# Simple_-V10.net
KiCad netlist of a schematic drawn in EasyEDA Pro
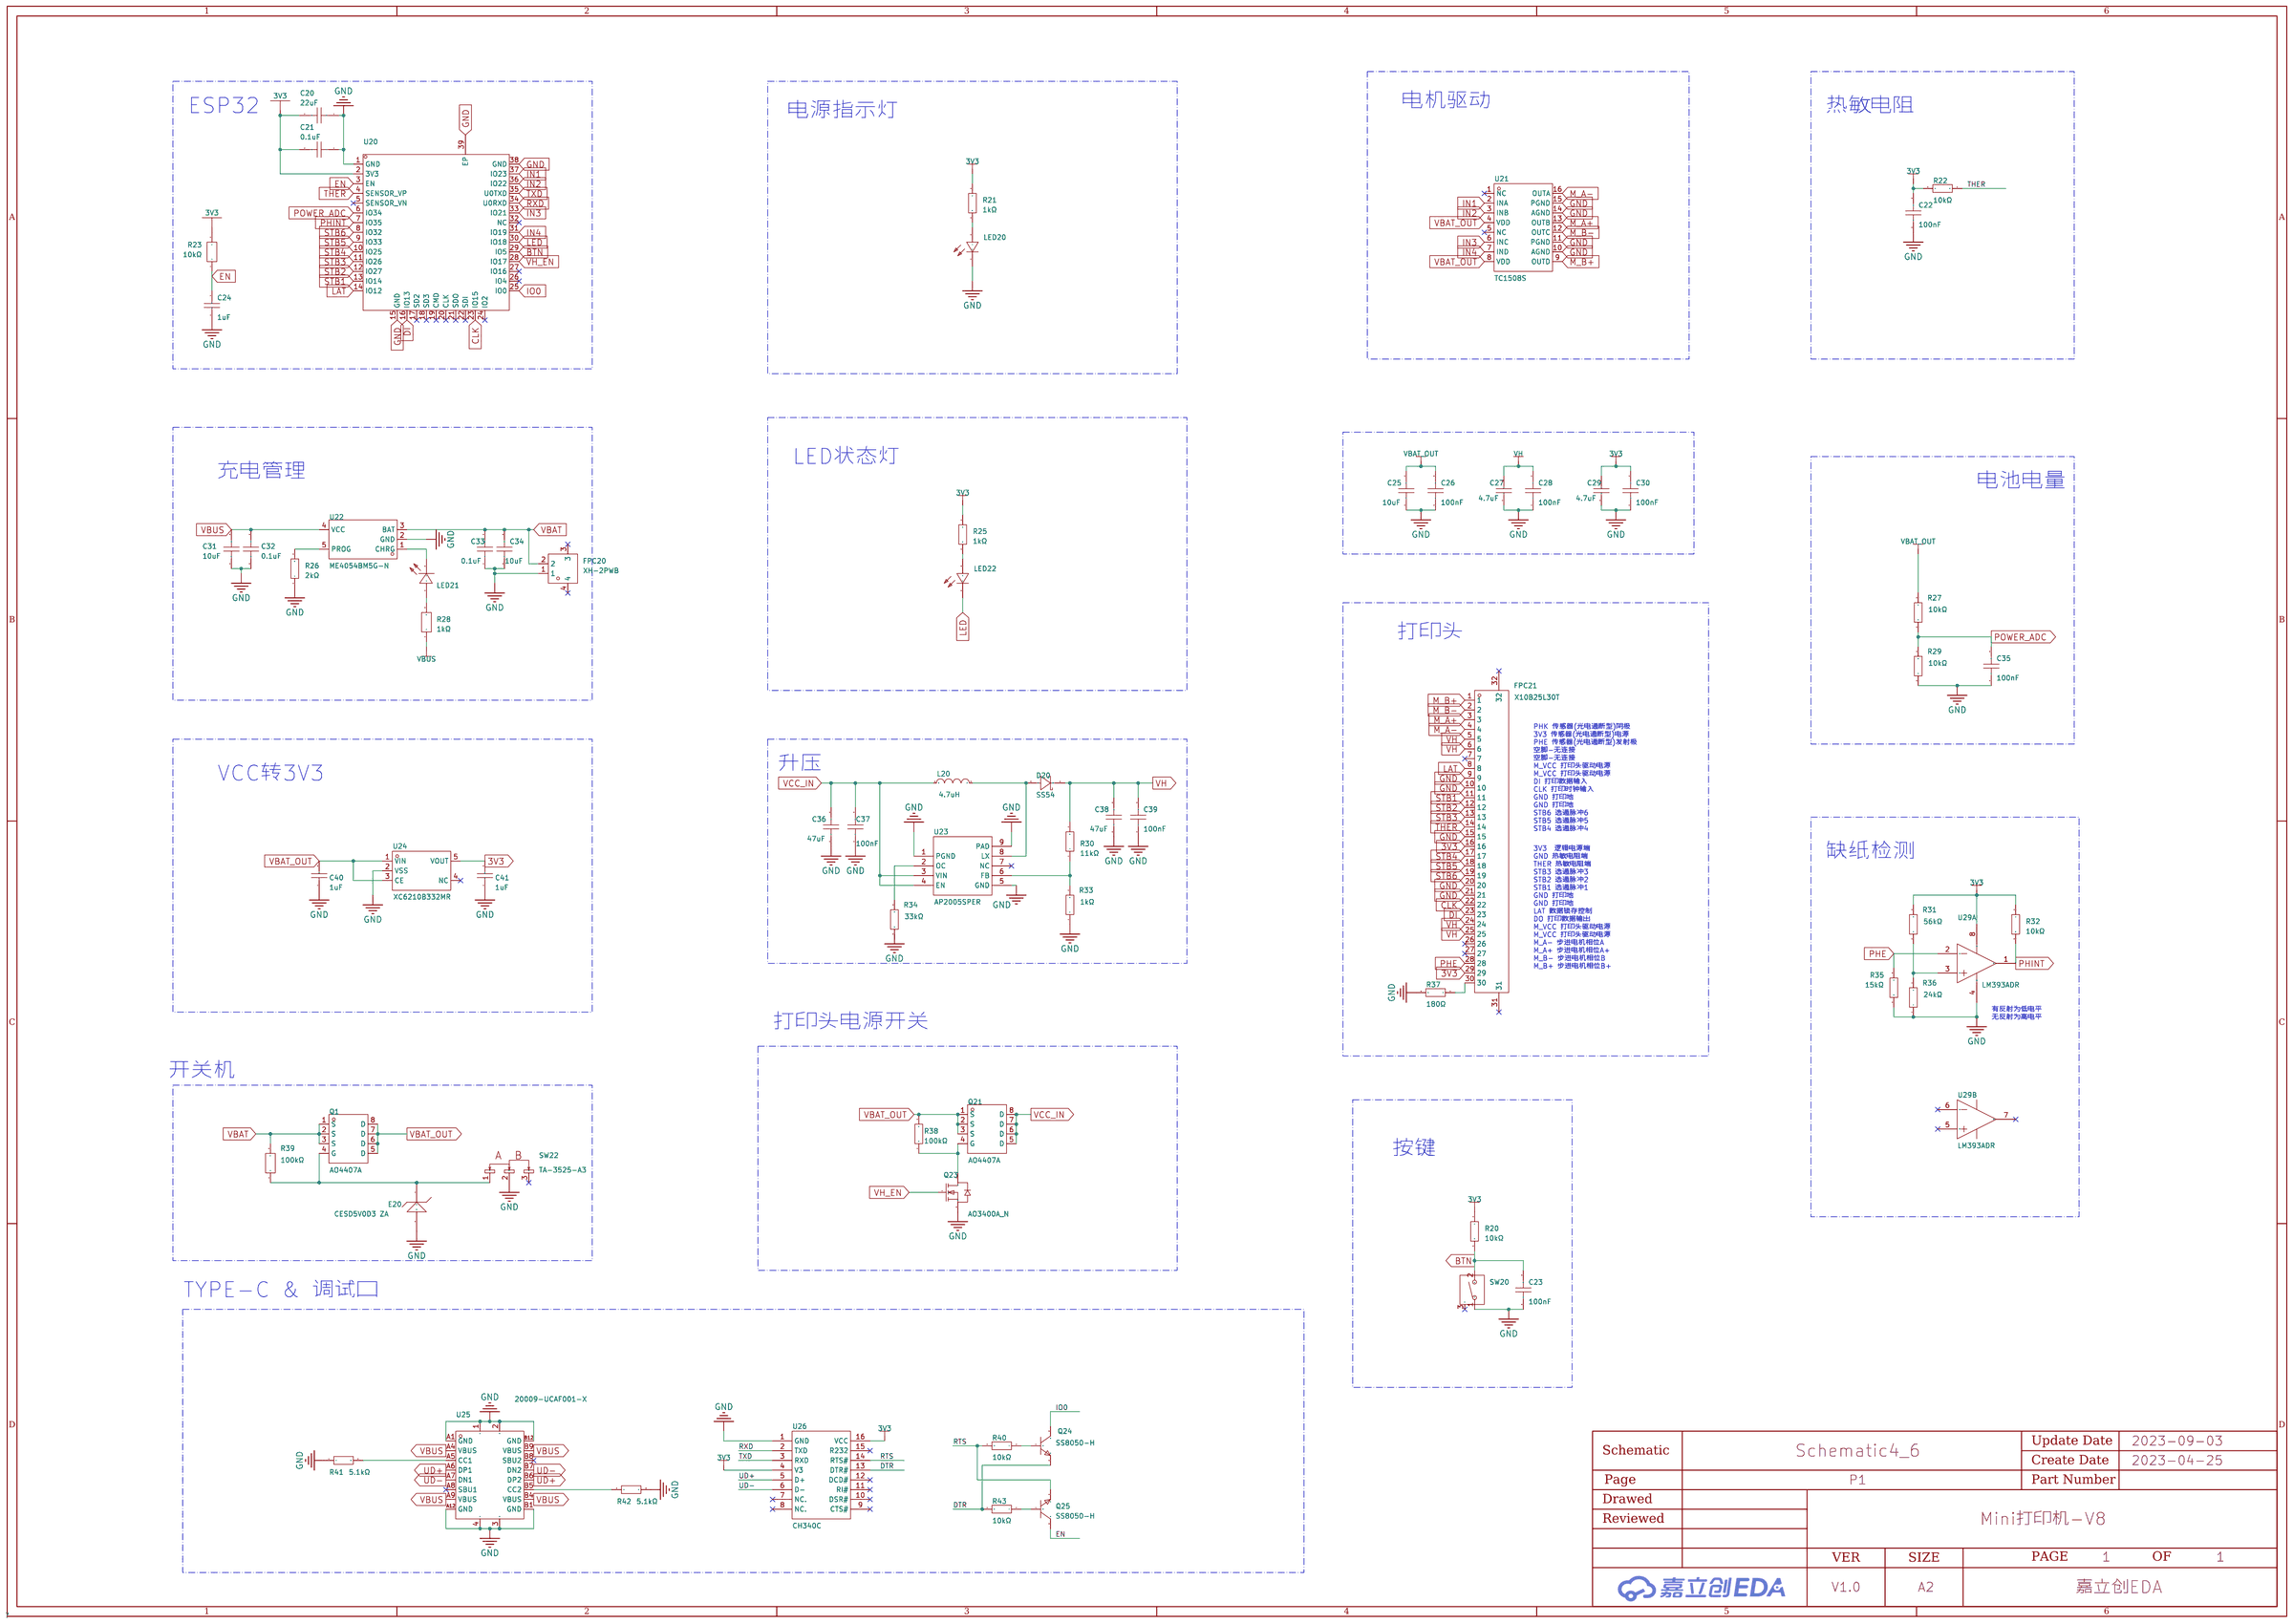
[diagram p0: schematic sheet]

(export (version "E")
  (design (tool "Eeschema 10.0.6"))
  (components
    (comp (ref "C20")
      (value "22uF")
      (footprint "easyedapro:c0603")
      (description "容值:22uF;精度:±0.25pF;额定电压:50V;温度系数:NP0;")
      (fields (field (name "Manufacturer Part") "MT18N1R5C500CT") (field (name "Manufacturer") "华新科(Walsin)"))
      (libsource (lib "easyedapro") (part "mt18n1r5c500ct"))
    )
    (comp (ref "C21")
      (value "0.1uF")
      (footprint "easyedapro:c0603")
      (description "容值：100nF 精度：±10% 额定电压：50V 材质(温度系数)：X7R 材质:X7R")
      (fields (field (name "Manufacturer Part") "MT18N1R5C500CT") (field (name "Manufacturer") "华新科(Walsin)"))
      (libsource (lib "easyedapro") (part "mt18n1r5c500ct"))
    )
    (comp (ref "C22")
      (value "100nF")
      (footprint "easyedapro:C0603")
      (description "容值:100nF;精度:±10%;额定电压:50V;材质(温度系数):X7R;")
      (fields
        (field (name "Manufacturer Part") "CL10B104KB8NNNC")
        (field (name "Manufacturer") "SAMSUNG(三星)")
      )
      (libsource (lib "easyedapro") (part "CL10B104KB8NNNC"))
    )
    (comp (ref "C23")
      (value "100nF")
      (footprint "easyedapro:C0603")
      (description "容值:100nF;精度:±10%;额定电压:50V;材质(温度系数):X7R;")
      (fields
        (field (name "Manufacturer Part") "CL10B104KB8NNNC")
        (field (name "Manufacturer") "SAMSUNG(三星)")
      )
      (libsource (lib "easyedapro") (part "CL10B104KB8NNNC"))
    )
    (comp (ref "C24")
      (value "1uF")
      (footprint "easyedapro:C0603")
      (description "容值:1uF;精度:±10%;额定电压:50V;材质(温度系数):X5R;")
      (fields
        (field (name "Manufacturer Part") "CL10A105KB8NNNC")
        (field (name "Manufacturer") "SAMSUNG(三星)")
      )
      (libsource (lib "easyedapro") (part "CL10A105KB8NNNC"))
    )
    (comp (ref "C25")
      (value "10uF")
      (footprint "easyedapro:C0603")
      (description "容值:10uF;精度:±20%;额定电压:25V;材质(温度系数):X5R;")
      (fields
        (field (name "Manufacturer Part") "CL10A106MA8NRNC")
        (field (name "Manufacturer") "SAMSUNG(三星)")
      )
      (libsource (lib "easyedapro") (part "CL10A106MA8NRNC"))
    )
    (comp (ref "C26")
      (value "100nF")
      (footprint "easyedapro:C0603")
      (description "容值:100nF;精度:±10%;额定电压:50V;材质(温度系数):X7R;")
      (fields
        (field (name "Manufacturer Part") "CL10B104KB8NNNC")
        (field (name "Manufacturer") "SAMSUNG(三星)")
      )
      (libsource (lib "easyedapro") (part "CL10B104KB8NNNC"))
    )
    (comp (ref "C27")
      (value "4.7uF")
      (footprint "easyedapro:C0603")
      (description "容值:4.7uF;精度:±10%;额定电压:25V;材质(温度系数):X5R;")
      (fields
        (field (name "Manufacturer Part") "CL10A475KA8NQNC")
        (field (name "Manufacturer") "SAMSUNG(三星)")
      )
      (libsource (lib "easyedapro") (part "CL10A475KA8NQNC"))
    )
    (comp (ref "C28")
      (value "100nF")
      (footprint "easyedapro:C0603")
      (description "容值:100nF;精度:±10%;额定电压:50V;材质(温度系数):X7R;")
      (fields
        (field (name "Manufacturer Part") "CL10B104KB8NNNC")
        (field (name "Manufacturer") "SAMSUNG(三星)")
      )
      (libsource (lib "easyedapro") (part "CL10B104KB8NNNC"))
    )
    (comp (ref "C29")
      (value "4.7uF")
      (footprint "easyedapro:C0603")
      (description "容值:4.7uF;精度:±10%;额定电压:25V;材质(温度系数):X5R;")
      (fields
        (field (name "Manufacturer Part") "CL10A475KA8NQNC")
        (field (name "Manufacturer") "SAMSUNG(三星)")
      )
      (libsource (lib "easyedapro") (part "CL10A475KA8NQNC"))
    )
    (comp (ref "C30")
      (value "100nF")
      (footprint "easyedapro:C0603")
      (description "容值:100nF;精度:±10%;额定电压:50V;材质(温度系数):X7R;")
      (fields
        (field (name "Manufacturer Part") "CL10B104KB8NNNC")
        (field (name "Manufacturer") "SAMSUNG(三星)")
      )
      (libsource (lib "easyedapro") (part "CL10B104KB8NNNC"))
    )
    (comp (ref "C31")
      (value "10uF")
      (fields
        (field (name "Manufacturer Part") "CL10A106MA8NRNC")
        (field (name "Manufacturer") "SAMSUNG(三星)")
      )
      (libsource (lib "easyedapro") (part "CL10A106MA8NRNC"))
    )
    (comp (ref "C32")
      (value "0.1uF")
      (footprint "easyedapro:c0603")
      (description "容值：100nF 精度：±10% 额定电压：50V 材质(温度系数)：X7R 材质:X7R")
      (fields (field (name "Manufacturer Part") "MT18N1R5C500CT") (field (name "Manufacturer") "华新科(Walsin)"))
      (libsource (lib "easyedapro") (part "mt18n1r5c500ct"))
    )
    (comp (ref "C33")
      (value "0.1uF")
      (footprint "easyedapro:c0603")
      (description "容值：100nF 精度：±10% 额定电压：50V 材质(温度系数)：X7R 材质:X7R")
      (fields (field (name "Manufacturer Part") "MT18N1R5C500CT") (field (name "Manufacturer") "华新科(Walsin)"))
      (libsource (lib "easyedapro") (part "mt18n1r5c500ct"))
    )
    (comp (ref "C34")
      (value "10uF")
      (fields
        (field (name "Manufacturer Part") "CL10A106MA8NRNC")
        (field (name "Manufacturer") "SAMSUNG(三星)")
      )
      (libsource (lib "easyedapro") (part "CL10A106MA8NRNC"))
    )
    (comp (ref "C35")
      (value "100nF")
      (footprint "easyedapro:C0603")
      (description "容值:100nF;精度:±10%;额定电压:50V;材质(温度系数):X7R;")
      (fields
        (field (name "Manufacturer Part") "CL10B104KB8NNNC")
        (field (name "Manufacturer") "SAMSUNG(三星)")
      )
      (libsource (lib "easyedapro") (part "CL10B104KB8NNNC"))
    )
    (comp (ref "C36")
      (value "47uF")
      (footprint "easyedapro:C1206")
      (description "容值:47uF;精度:±20%;额定电压:10V;材质(温度系数):X5R;")
      (fields
        (field (name "Manufacturer Part") "CL31A476MPHNNNE")
        (field (name "Manufacturer") "SAMSUNG(三星)")
      )
      (libsource (lib "easyedapro") (part "CL31A476MPHNNNE"))
    )
    (comp (ref "C37")
      (value "100nF")
      (footprint "easyedapro:C0603")
      (description "容值:100nF;精度:±10%;额定电压:50V;材质(温度系数):X7R;")
      (fields
        (field (name "Manufacturer Part") "CL10B104KB8NNNC")
        (field (name "Manufacturer") "SAMSUNG(三星)")
      )
      (libsource (lib "easyedapro") (part "CL10B104KB8NNNC"))
    )
    (comp (ref "C38")
      (value "47uF")
      (footprint "easyedapro:C1206")
      (description "容值:47uF;精度:±20%;额定电压:10V;材质(温度系数):X5R;")
      (fields
        (field (name "Manufacturer Part") "CL31A476MPHNNNE")
        (field (name "Manufacturer") "SAMSUNG(三星)")
      )
      (libsource (lib "easyedapro") (part "CL31A476MPHNNNE"))
    )
    (comp (ref "C39")
      (value "100nF")
      (footprint "easyedapro:C0603")
      (description "容值:100nF;精度:±10%;额定电压:50V;材质(温度系数):X7R;")
      (fields
        (field (name "Manufacturer Part") "CL10B104KB8NNNC")
        (field (name "Manufacturer") "SAMSUNG(三星)")
      )
      (libsource (lib "easyedapro") (part "CL10B104KB8NNNC"))
    )
    (comp (ref "C40")
      (value "1uF")
      (footprint "easyedapro:C0603")
      (description "容值:1uF;精度:±10%;额定电压:50V;材质(温度系数):X5R;")
      (fields
        (field (name "Manufacturer Part") "CL10A105KB8NNNC")
        (field (name "Manufacturer") "SAMSUNG(三星)")
      )
      (libsource (lib "easyedapro") (part "CL10A105KB8NNNC"))
    )
    (comp (ref "C41")
      (value "1uF")
      (footprint "easyedapro:C0603")
      (description "容值:1uF;精度:±10%;额定电压:50V;材质(温度系数):X5R;")
      (fields
        (field (name "Manufacturer Part") "CL10A105KB8NNNC")
        (field (name "Manufacturer") "SAMSUNG(三星)")
      )
      (libsource (lib "easyedapro") (part "CL10A105KB8NNNC"))
    )
    (comp (ref "D20")
      (value "SS54")
      (footprint "easyedapro:SMA_L4.3-W2.6-LS5.0-RD")
      (description "二极管配置:独立式;直流反向耐压(Vr):40V;平均整流电流(Io):5A;正向压降(Vf):550mV@5A;反向电流(Ir):500uA@40V;")
      (fields (field (name "Manufacturer") "TWGMC(台湾迪嘉)"))
      (libsource (lib "easyedapro") (part "SS54_C727065"))
    )
    (comp (ref "E20")
      (value "CESD5V0D3 ZA")
      (footprint "easyedapro:SOD-323_L1.8-W1.3-LS2.5-RD")
      (description "极性:单向;反向截止电压(Vrwm):5V;击穿电压(VBR):6.2V;峰值脉冲电流(Ipp)@8/20us:15A;钳位电压(Vc)@Ipp:15.5V;")
      (fields (field (name "Manufacturer") "CJ(江苏长电/长晶)"))
      (libsource (lib "easyedapro") (part "CESD5V0D3 ZA"))
    )
    (comp (ref "FPC20")
      (value "XH-2PWB")
      (footprint "easyedapro:CONN-SMD_2P-P2.50_DEALON_XH-2PWB_C2905024")
      (description "参考系列:XH;间距:2.5mm;插针结构:1x2P;排数:1;每排PIN数:2;行距:-;公母:公型插针;安装方式:卧贴;额定电流:3A;工作温度范围:-25~+85;")
      (fields (field (name "Manufacturer") "DEALON(德艺隆)"))
      (libsource (lib "easyedapro") (part "XH-2PWB_C2905024"))
    )
    (comp (ref "FPC21")
      (value "X10B25L30T")
      (footprint "easyedapro:FPC-SMD_X10B25U30T")
      (description "间距:1mm;触点数量:30;锁定特性:抽屉式;安装类型:卧贴;触点类型:下接;工作温度范围:-40~+85;焊接温度(最大值):260;")
      (fields (field (name "Manufacturer") "XKB Connectivity(中国星坤)"))
      (libsource (lib "easyedapro") (part "X10B25L30T"))
    )
    (comp (ref "L20")
      (value "4.7uH")
      (footprint "easyedapro:IND-SMD_L6.0-W6.0")
      (description "电感值:4.7uH;精度:±20%;额定电流:4A;直流电阻(DCR):27.6mΩ;")
      (fields (field (name "Manufacturer Part") "1255AY-4R7M=P3") (field (name "Manufacturer") "muRata(村田)"))
      (libsource (lib "easyedapro") (part "1255AY-4R7M=P3"))
    )
    (comp (ref "LED20")
      (value "NCD0603R1")
      (footprint "easyedapro:LED0603-RD_RED")
      (description "发光颜色:红灯;")
      (fields (field (name "Manufacturer") "国星光电"))
      (libsource (lib "easyedapro") (part "FC-DA1608HRK-620D"))
    )
    (comp (ref "LED21")
      (value "TLMG1100-GS08")
      (footprint "easyedapro:LED0603-R-RD_GREEN")
      (description "照明颜色:普绿/黄绿;色温 - CCT（K）:-;主波长/色坐标:570nm;")
      (fields (field (name "Manufacturer") "VISHAY(威世)"))
      (libsource (lib "easyedapro") (part "TLMG1100-GS08"))
    )
    (comp (ref "LED22")
      (value "NCD0603R1")
      (footprint "easyedapro:LED0603-RD_RED")
      (description "发光颜色:红灯;")
      (fields (field (name "Manufacturer") "国星光电"))
      (libsource (lib "easyedapro") (part "FC-DA1608HRK-620D"))
    )
    (comp (ref "Q1")
      (value "AO4407A")
      (footprint "easyedapro:SOP-8_L5.0-W4.0-P1.27-LS6.0-BL")
      (fields (field (name "Manufacturer") "UMW(友台半导体)"))
      (libsource (lib "easyedapro") (part "AO4407A_C2841482"))
    )
    (comp (ref "Q21")
      (value "AO4407A")
      (footprint "easyedapro:SOP-8_L5.0-W4.0-P1.27-LS6.0-BL")
      (fields (field (name "Manufacturer") "UMW(友台半导体)"))
      (libsource (lib "easyedapro") (part "AO4407A_C2841482"))
    )
    (comp (ref "Q23")
      (value "AO3400A_N")
      (footprint "easyedapro:SOT-23-3_L2.9-W1.3-P1.90-LS2.4-BR")
      (fields (field (name "Manufacturer Part") "AO3400A") (field (name "Manufacturer") "UMW(友台半导体)"))
      (libsource (lib "easyedapro") (part "AO3400A_C347475"))
    )
    (comp (ref "Q24")
      (value "SS8050-H")
      (footprint "easyedapro:SOT-23-3_L2.9-W1.3-P1.90-LS2.4-BR")
      (fields (field (name "Manufacturer") "YANGJIE(扬杰)"))
      (libsource (lib "easyedapro") (part "SS8050-H"))
    )
    (comp (ref "Q25")
      (value "SS8050-H")
      (footprint "easyedapro:SOT-23-3_L2.9-W1.3-P1.90-LS2.4-BR")
      (fields (field (name "Manufacturer") "YANGJIE(扬杰)"))
      (libsource (lib "easyedapro") (part "SS8050-H"))
    )
    (comp (ref "R20")
      (value "10kΩ")
      (footprint "easyedapro:R0603")
      (description "阻值:10kΩ;精度:±1%;功率:100mW;温度系数:±100ppm/;最大工作电压:-;工作温度范围:-55~+155;")
      (fields (field (name "Manufacturer Part") "ERJ3EKF1002V") (field (name "Manufacturer") "PANASONIC(松下)"))
      (libsource (lib "easyedapro") (part "ERJ-3EKF1002V"))
    )
    (comp (ref "R21")
      (value "1kΩ")
      (footprint "easyedapro:R0603")
      (description "阻值:1kΩ;精度:±1%;功率:100mW;")
      (fields (field (name "Manufacturer Part") "RMC06031K1%N") (field (name "Manufacturer") "Tyohm(幸亚电阻)"))
      (libsource (lib "easyedapro") (part "RMC06031K1%N"))
    )
    (comp (ref "R22")
      (value "10kΩ")
      (footprint "easyedapro:R0603")
      (description "电阻类型:厚膜电阻;阻值:10kΩ;精度:±1%;功率:100mW;温度系数:±100ppm/;最大工作电压:75V;工作温度范围:-55~+155;")
      (fields
        (field (name "Manufacturer Part") "0603WAF1002T5E")
        (field (name "Manufacturer") "UNI-ROYAL(厚声)")
      )
      (libsource (lib "easyedapro") (part "0603WAF1002T5E"))
    )
    (comp (ref "R23")
      (value "10kΩ")
      (footprint "easyedapro:r0603")
      (description "阻值:10kΩ;精度:±1%;功率:-;温度系数:-;")
      (fields (field (name "Manufacturer Part") "SG73P1JTTD1002F") (field (name "Manufacturer") "KOA"))
      (libsource (lib "easyedapro") (part "sg73p1jttd1002f"))
    )
    (comp (ref "R25")
      (value "1kΩ")
      (footprint "easyedapro:R0603")
      (description "阻值:1kΩ;精度:±1%;功率:100mW;")
      (fields (field (name "Manufacturer Part") "RMC06031K1%N") (field (name "Manufacturer") "Tyohm(幸亚电阻)"))
      (libsource (lib "easyedapro") (part "RMC06031K1%N"))
    )
    (comp (ref "R26")
      (value "2kΩ")
      (description "精度:±1%;阻值:2kΩ;温度系数:±100ppm/;功率:1/10W;最大工作电压:75V;工作温度范围:-55~+155;")
      (fields
        (field (name "Manufacturer Part") "0603WAF2001T5E")
        (field (name "Manufacturer") "UNI-ROYAL(厚声)")
      )
      (libsource (lib "easyedapro") (part "0603WAF2001T5E"))
    )
    (comp (ref "R27")
      (value "10kΩ")
      (footprint "easyedapro:R0603")
      (description "电阻类型:厚膜电阻;阻值:10kΩ;精度:±1%;功率:100mW;温度系数:±100ppm/;最大工作电压:75V;工作温度范围:-55~+155;")
      (fields
        (field (name "Manufacturer Part") "0603WAF1002T5E")
        (field (name "Manufacturer") "UNI-ROYAL(厚声)")
      )
      (libsource (lib "easyedapro") (part "0603WAF1002T5E"))
    )
    (comp (ref "R28")
      (value "1kΩ")
      (footprint "easyedapro:R0603")
      (fields (field (name "Manufacturer Part") "ERA3VEB1001V") (field (name "Manufacturer") "PANASONIC(松下)"))
      (libsource (lib "easyedapro") (part "ERA3VEB1001V"))
    )
    (comp (ref "R29")
      (value "10kΩ")
      (footprint "easyedapro:R0603")
      (description "电阻类型:厚膜电阻;阻值:10kΩ;精度:±1%;功率:100mW;温度系数:±100ppm/;最大工作电压:75V;工作温度范围:-55~+155;")
      (fields
        (field (name "Manufacturer Part") "0603WAF1002T5E")
        (field (name "Manufacturer") "UNI-ROYAL(厚声)")
      )
      (libsource (lib "easyedapro") (part "0603WAF1002T5E"))
    )
    (comp (ref "R30")
      (value "11kΩ")
      (footprint "easyedapro:R0603")
      (description "电阻类型:厚膜电阻;阻值:11kΩ;精度:±5%;功率:100mW;温度系数:±100ppm/;最大工作电压:75V;工作温度范围:-55~+155;")
      (fields
        (field (name "Manufacturer Part") "0603WAJ0113T5E")
        (field (name "Manufacturer") "UNI-ROYAL(厚声)")
      )
      (libsource (lib "easyedapro") (part "0603WAJ0113T5E"))
    )
    (comp (ref "R31")
      (value "56kΩ")
      (footprint "easyedapro:R0603")
      (description "电阻类型:厚膜电阻;阻值:56kΩ;精度:±1%;功率:100mW;温度系数:±100ppm/;最大工作电压:75V;工作温度范围:-55~+155;")
      (fields
        (field (name "Manufacturer Part") "0603WAF5602T5E")
        (field (name "Manufacturer") "UNI-ROYAL(厚声)")
      )
      (libsource (lib "easyedapro") (part "0603WAF5602T5E"))
    )
    (comp (ref "R32")
      (value "10kΩ")
      (footprint "easyedapro:R0603")
      (description "电阻类型:厚膜电阻;阻值:10kΩ;精度:±1%;功率:100mW;温度系数:±100ppm/;最大工作电压:75V;工作温度范围:-55~+155;")
      (fields
        (field (name "Manufacturer Part") "0603WAF1002T5E")
        (field (name "Manufacturer") "UNI-ROYAL(厚声)")
      )
      (libsource (lib "easyedapro") (part "0603WAF1002T5E"))
    )
    (comp (ref "R33")
      (value "1kΩ")
      (footprint "easyedapro:R0603")
      (description "阻值:1kΩ;精度:±1%;功率:100mW;")
      (fields (field (name "Manufacturer Part") "RMC06031K1%N") (field (name "Manufacturer") "Tyohm(幸亚电阻)"))
      (libsource (lib "easyedapro") (part "RMC06031K1%N"))
    )
    (comp (ref "R34")
      (value "33kΩ")
      (footprint "easyedapro:R0603")
      (description "电阻类型:厚膜电阻;阻值:33kΩ;精度:±1%;功率:100mW;温度系数:±100ppm/;最大工作电压:75V;工作温度范围:-55~+155;")
      (fields
        (field (name "Manufacturer Part") "0603WAF3302T5E")
        (field (name "Manufacturer") "UNI-ROYAL(厚声)")
      )
      (libsource (lib "easyedapro") (part "0603WAF3302T5E"))
    )
    (comp (ref "R35")
      (value "15kΩ")
      (footprint "easyedapro:R0603")
      (description "电阻类型:厚膜电阻;阻值:15kΩ;精度:±1%;功率:100mW;温度系数:±100ppm/;最大工作电压:75V;工作温度范围:-55~+155;")
      (fields
        (field (name "Manufacturer Part") "0603WAF1502T5E")
        (field (name "Manufacturer") "UNI-ROYAL(厚声)")
      )
      (libsource (lib "easyedapro") (part "0603WAF1502T5E"))
    )
    (comp (ref "R36")
      (value "24kΩ")
      (footprint "easyedapro:R0603")
      (description "电阻类型:厚膜电阻;阻值:24kΩ;精度:±1%;功率:100mW;温度系数:±100ppm/;最大工作电压:75V;工作温度范围:-55~+155;")
      (fields
        (field (name "Manufacturer Part") "0603WAF2402T5E")
        (field (name "Manufacturer") "UNI-ROYAL(厚声)")
      )
      (libsource (lib "easyedapro") (part "0603WAF2402T5E"))
    )
    (comp (ref "R37")
      (value "180Ω")
      (footprint "easyedapro:R0603")
      (description "电阻类型:厚膜电阻;阻值:180Ω;精度:±1%;功率:100mW;温度系数:±100ppm/;最大工作电压:75V;工作温度范围:-55~+155;")
      (fields
        (field (name "Manufacturer Part") "0603WAF1800T5E")
        (field (name "Manufacturer") "UNI-ROYAL(厚声)")
      )
      (libsource (lib "easyedapro") (part "0603WAF1800T5E"))
    )
    (comp (ref "R38")
      (value "100kΩ")
      (footprint "easyedapro:R0603")
      (description "电阻类型:厚膜电阻;阻值:100kΩ;精度:±1%;功率:100mW;温度系数:±100ppm/;最大工作电压:75V;工作温度范围:-55~+155;")
      (fields
        (field (name "Manufacturer Part") "0603WAF1003T5E")
        (field (name "Manufacturer") "UNI-ROYAL(厚声)")
      )
      (libsource (lib "easyedapro") (part "0603WAF1003T5E"))
    )
    (comp (ref "R39")
      (value "100kΩ")
      (footprint "easyedapro:R0603")
      (fields (field (name "Manufacturer Part") "ERA3VEB1003V") (field (name "Manufacturer") "PANASONIC(松下)"))
      (libsource (lib "easyedapro") (part "ERA3VEB1003V"))
    )
    (comp (ref "R40")
      (value "10kΩ")
      (footprint "easyedapro:R0603")
      (description "阻值:10kΩ;精度:±1%;功率:100mW;温度系数:±100ppm/;最大工作电压:-;工作温度范围:-55~+155;")
      (fields (field (name "Manufacturer Part") "ERJ3EKF1002V") (field (name "Manufacturer") "PANASONIC(松下)"))
      (libsource (lib "easyedapro") (part "ERJ-3EKF1002V"))
    )
    (comp (ref "R41")
      (value "5.1kΩ")
      (footprint "easyedapro:R0603")
      (description "电阻类型:厚膜电阻;阻值:5.1kΩ;精度:±1%;功率:100mW;温度系数:±100ppm/;最大工作电压:75V;工作温度范围:-55~+155;")
      (fields
        (field (name "Manufacturer Part") "0603WAF5101T5E")
        (field (name "Manufacturer") "UNI-ROYAL(厚声)")
      )
      (libsource (lib "easyedapro") (part "0603WAF5101T5E"))
    )
    (comp (ref "R42")
      (value "5.1kΩ")
      (footprint "easyedapro:R0603")
      (description "电阻类型:厚膜电阻;阻值:5.1kΩ;精度:±1%;功率:100mW;温度系数:±100ppm/;最大工作电压:75V;工作温度范围:-55~+155;")
      (fields
        (field (name "Manufacturer Part") "0603WAF5101T5E")
        (field (name "Manufacturer") "UNI-ROYAL(厚声)")
      )
      (libsource (lib "easyedapro") (part "0603WAF5101T5E"))
    )
    (comp (ref "R43")
      (value "10kΩ")
      (footprint "easyedapro:R0603")
      (description "阻值:10kΩ;精度:±1%;功率:100mW;温度系数:±100ppm/;最大工作电压:-;工作温度范围:-55~+155;")
      (fields (field (name "Manufacturer Part") "ERJ3EKF1002V") (field (name "Manufacturer") "PANASONIC(松下)"))
      (libsource (lib "easyedapro") (part "ERJ-3EKF1002V"))
    )
    (comp (ref "SW20")
      (value "TS4538B3JTP 250gf 121")
      (footprint "easyedapro:KEY-SMD_3P-L4.5-W3.8-P3.00-LS4.5-BL")
      (fields (field (name "Manufacturer") "SHOU HAN(首韩)"))
      (libsource (lib "easyedapro") (part "TS4538B3JTP 250GF 121"))
    )
    (comp (ref "SW22")
      (value "TA-3525-A3")
      (footprint "easyedapro:SW-SMD_3P-L9.1-W3.5-P2.50-EH6.8")
      (fields (field (name "Manufacturer") "Yuandi(元迪)"))
      (libsource (lib "easyedapro") (part "TA-3525-A3"))
    )
    (comp (ref "U20")
      (value "~")
      (footprint "easyedapro:wirelm-smd_esp32-s")
      (fields (field (name "Manufacturer Part") "ESP32-S") (field (name "Manufacturer") "Ai-Thinker(安信可)"))
      (libsource (lib "easyedapro") (part "esp32-s"))
    )
    (comp (ref "U21")
      (value "TC1508S")
      (footprint "easyedapro:SOP-16_L10.0-W3.9-P1.27-LS6.0-BL")
      (description "双通道直流马达驱动器")
      (fields (field (name "Manufacturer") "FM富满"))
      (libsource (lib "easyedapro") (part "TC1508S"))
    )
    (comp (ref "U22")
      (value "ME4054BM5G-N")
      (footprint "easyedapro:TSOT-23-5_L2.9-W1.6-P0.95-LS2.8-BL")
      (fields (field (name "Manufacturer") "MICRONE(南京微盟)"))
      (libsource (lib "easyedapro") (part "ME4054BM5G-N"))
    )
    (comp (ref "U23")
      (value "AP2005SPER")
      (footprint "easyedapro:ESOP-8_L4.9-W3.9-P1.27-LS6.0-BL-EP")
      (description "功能类型:升压型;同步整流:否;输出通道数:1;拓扑结构:升压式;输入电压:2.5V~5.5V;输出电压:9V;输出电流(最大值):-;开关频率:1MHz;")
      (fields (field (name "Manufacturer") "chipown(芯朋微电子)"))
      (libsource (lib "easyedapro") (part "AP2005SPER"))
    )
    (comp (ref "U24")
      (value "XC6210B332MR")
      (footprint "easyedapro:TSOT-23-5_L2.9-W1.6-P0.95-LS2.8-BR")
      (description "输出类型:固定;输出极性:正;输出通道数:1;最大输入电压:6V;输出电压:3.3V;压差:75mV@(100mA);输出电流:900mA;电源纹波抑制比(PSRR):60dB@(1kHz);")
      (fields (field (name "Manufacturer") "TOREX(特瑞仕)"))
      (libsource (lib "easyedapro") (part "XC6210B332MR_C424705"))
    )
    (comp (ref "U25")
      (value "20009-UCAF001-X")
      (footprint "easyedapro:TYPE-C-SMD_20009-UCAF001-X")
      (fields (field (name "Manufacturer") "MINTRON(明硕)"))
      (libsource (lib "easyedapro") (part "20009-UCAF001-X"))
    )
    (comp (ref "U26")
      (value "CH340C")
      (footprint "easyedapro:SOP-16_L10.0-W3.9-P1.27-LS6.0-BL")
      (description "类型:Transceiver;协议类别:USB 2.0;驱动器/接收器数:-;数据速率:2Mbps;")
      (fields (field (name "Manufacturer") "WCH(南京沁恒)"))
      (libsource (lib "easyedapro") (part "CH340C"))
    )
    (comp (ref "U29")
      (value "LM393ADR")
      (footprint "easyedapro:SOP-8_L4.9-W3.9-P1.27-LS6.0-BL")
      (fields (field (name "Manufacturer") "UMW(广东友台半导体)"))
      (libsource (lib "easyedapro") (part "LM393ADR_C404321"))
    )
  )
  (nets
    (net (code "1") (name "/DTR") (class "Default")
      (node (ref "Q24") (pin "2") (pinfunction "E_2") (pintype "input"))
      (node (ref "R43") (pin "2") (pinfunction "2_2") (pintype "input"))
      (node (ref "U26") (pin "13") (pinfunction "DTR#_13") (pintype "input"))
    )
    (net (code "2") (name "/RTS") (class "Default")
      (node (ref "Q25") (pin "2") (pinfunction "E_2") (pintype "input"))
      (node (ref "R40") (pin "2") (pinfunction "2_2") (pintype "input"))
      (node (ref "U26") (pin "14") (pinfunction "RTS#_14") (pintype "input"))
    )
    (net (code "3") (name "3V3") (class "Default")
      (node (ref "C20") (pin "2") (pinfunction "2_2") (pintype "input"))
      (node (ref "C21") (pin "2") (pinfunction "2_2") (pintype "input"))
      (node (ref "C22") (pin "2") (pinfunction "2_2") (pintype "input"))
      (node (ref "C29") (pin "2") (pinfunction "2_2") (pintype "input"))
      (node (ref "C30") (pin "2") (pinfunction "2_2") (pintype "input"))
      (node (ref "C41") (pin "2") (pinfunction "2_2") (pintype "input"))
      (node (ref "FPC21") (pin "16") (pinfunction "16_16") (pintype "input"))
      (node (ref "FPC21") (pin "29") (pinfunction "29_29") (pintype "input"))
      (node (ref "R20") (pin "1") (pinfunction "1_1") (pintype "input"))
      (node (ref "R21") (pin "1") (pinfunction "1_1") (pintype "input"))
      (node (ref "R22") (pin "2") (pinfunction "2_2") (pintype "input"))
      (node (ref "R23") (pin "2") (pinfunction "2_2") (pintype "input"))
      (node (ref "R25") (pin "1") (pinfunction "1_1") (pintype "input"))
      (node (ref "R31") (pin "2") (pinfunction "2_2") (pintype "input"))
      (node (ref "R32") (pin "1") (pinfunction "1_1") (pintype "input"))
      (node (ref "U20") (pin "2") (pinfunction "3V3_2") (pintype "input"))
      (node (ref "U24") (pin "5") (pinfunction "VOUT_5") (pintype "input"))
      (node (ref "U26") (pin "16") (pinfunction "VCC_16") (pintype "input"))
      (node (ref "U26") (pin "4") (pinfunction "V3_4") (pintype "input"))
      (node (ref "U29") (pin "8") (pinfunction "VCC_8") (pintype "input"))
    )
    (net (code "4") (name "BTN") (class "Default")
      (node (ref "C23") (pin "2") (pinfunction "2_2") (pintype "input"))
      (node (ref "R20") (pin "2") (pinfunction "2_2") (pintype "input"))
      (node (ref "SW20") (pin "2") (pinfunction "2_2") (pintype "input"))
      (node (ref "U20") (pin "29") (pinfunction "IO5_29") (pintype "input"))
    )
    (net (code "5") (name "CLK") (class "Default")
      (node (ref "FPC21") (pin "22") (pinfunction "22_22") (pintype "input"))
      (node (ref "U20") (pin "23") (pinfunction "IO15_23") (pintype "input"))
    )
    (net (code "6") (name "DI") (class "Default")
      (node (ref "FPC21") (pin "23") (pinfunction "23_23") (pintype "input"))
      (node (ref "U20") (pin "16") (pinfunction "IO13_16") (pintype "input"))
    )
    (net (code "7") (name "EN") (class "Default")
      (node (ref "C24") (pin "2") (pinfunction "2_2") (pintype "input"))
      (node (ref "Q25") (pin "3") (pinfunction "C_3") (pintype "input"))
      (node (ref "R23") (pin "1") (pinfunction "1_1") (pintype "input"))
      (node (ref "U20") (pin "3") (pinfunction "EN_3") (pintype "input"))
    )
    (net (code "8") (name "GND") (class "Default")
      (node (ref "C20") (pin "1") (pinfunction "1_1") (pintype "input"))
      (node (ref "C21") (pin "1") (pinfunction "1_1") (pintype "input"))
      (node (ref "C22") (pin "1") (pinfunction "1_1") (pintype "input"))
      (node (ref "C23") (pin "1") (pinfunction "1_1") (pintype "input"))
      (node (ref "C24") (pin "1") (pinfunction "1_1") (pintype "input"))
      (node (ref "C25") (pin "1") (pinfunction "1_1") (pintype "input"))
      (node (ref "C26") (pin "1") (pinfunction "1_1") (pintype "input"))
      (node (ref "C27") (pin "1") (pinfunction "1_1") (pintype "input"))
      (node (ref "C28") (pin "1") (pinfunction "1_1") (pintype "input"))
      (node (ref "C29") (pin "1") (pinfunction "1_1") (pintype "input"))
      (node (ref "C30") (pin "1") (pinfunction "1_1") (pintype "input"))
      (node (ref "C31") (pin "1") (pinfunction "1_1") (pintype "input"))
      (node (ref "C32") (pin "2") (pinfunction "2_2") (pintype "input"))
      (node (ref "C33") (pin "1") (pinfunction "1_1") (pintype "input"))
      (node (ref "C34") (pin "1") (pinfunction "1_1") (pintype "input"))
      (node (ref "C35") (pin "1") (pinfunction "1_1") (pintype "input"))
      (node (ref "C36") (pin "1") (pinfunction "1_1") (pintype "input"))
      (node (ref "C37") (pin "1") (pinfunction "1_1") (pintype "input"))
      (node (ref "C38") (pin "1") (pinfunction "1_1") (pintype "input"))
      (node (ref "C39") (pin "1") (pinfunction "1_1") (pintype "input"))
      (node (ref "C40") (pin "1") (pinfunction "1_1") (pintype "input"))
      (node (ref "C41") (pin "1") (pinfunction "1_1") (pintype "input"))
      (node (ref "E20") (pin "2") (pinfunction "2_2") (pintype "input"))
      (node (ref "FPC20") (pin "1") (pinfunction "1_1") (pintype "input"))
      (node (ref "FPC21") (pin "10") (pinfunction "10_10") (pintype "input"))
      (node (ref "FPC21") (pin "15") (pinfunction "15_15") (pintype "input"))
      (node (ref "FPC21") (pin "20") (pinfunction "20_20") (pintype "input"))
      (node (ref "FPC21") (pin "21") (pinfunction "21_21") (pintype "input"))
      (node (ref "FPC21") (pin "9") (pinfunction "9_9") (pintype "input"))
      (node (ref "LED20") (pin "1") (pinfunction "K_1") (pintype "input"))
      (node (ref "Q23") (pin "2") (pinfunction "S_2") (pintype "input"))
      (node (ref "R26") (pin "1") (pinfunction "1_1") (pintype "input"))
      (node (ref "R29") (pin "1") (pinfunction "1_1") (pintype "input"))
      (node (ref "R33") (pin "1") (pinfunction "1_1") (pintype "input"))
      (node (ref "R34") (pin "1") (pinfunction "1_1") (pintype "input"))
      (node (ref "R35") (pin "1") (pinfunction "1_1") (pintype "input"))
      (node (ref "R36") (pin "1") (pinfunction "1_1") (pintype "input"))
      (node (ref "R37") (pin "2") (pinfunction "2_2") (pintype "input"))
      (node (ref "R41") (pin "1") (pinfunction "1_1") (pintype "input"))
      (node (ref "R42") (pin "2") (pinfunction "2_2") (pintype "input"))
      (node (ref "SW20") (pin "1") (pinfunction "1_1") (pintype "input"))
      (node (ref "SW22") (pin "2") (pinfunction "2_2") (pintype "input"))
      (node (ref "U20") (pin "1") (pinfunction "GND_1") (pintype "input"))
      (node (ref "U20") (pin "15") (pinfunction "GND_15") (pintype "input"))
      (node (ref "U20") (pin "38") (pinfunction "GND_38") (pintype "input"))
      (node (ref "U20") (pin "39") (pinfunction "EP_39") (pintype "input"))
      (node (ref "U21") (pin "10") (pinfunction "AGND_10") (pintype "input"))
      (node (ref "U21") (pin "11") (pinfunction "PGND_11") (pintype "input"))
      (node (ref "U21") (pin "14") (pinfunction "AGND_14") (pintype "input"))
      (node (ref "U21") (pin "15") (pinfunction "PGND_15") (pintype "input"))
      (node (ref "U22") (pin "2") (pinfunction "GND_2") (pintype "input"))
      (node (ref "U23") (pin "1") (pinfunction "PGND_1") (pintype "input"))
      (node (ref "U23") (pin "5") (pinfunction "GND_5") (pintype "input"))
      (node (ref "U23") (pin "9") (pinfunction "PAD_9") (pintype "input"))
      (node (ref "U24") (pin "2") (pinfunction "VSS_2") (pintype "input"))
      (node (ref "U25") (pin "1") (pinfunction "1_1") (pintype "input"))
      (node (ref "U25") (pin "2") (pinfunction "2_2") (pintype "input"))
      (node (ref "U25") (pin "3") (pinfunction "3_3") (pintype "input"))
      (node (ref "U25") (pin "4") (pinfunction "4_4") (pintype "input"))
      (node (ref "U25") (pin "A1") (pinfunction "GND_A1") (pintype "input"))
      (node (ref "U25") (pin "A12") (pinfunction "GND_A12") (pintype "input"))
      (node (ref "U25") (pin "B1") (pinfunction "GND_B1") (pintype "input"))
      (node (ref "U25") (pin "B12") (pinfunction "GND_B12") (pintype "input"))
      (node (ref "U26") (pin "1") (pinfunction "GND_1") (pintype "input"))
      (node (ref "U29") (pin "4") (pinfunction "GND_4") (pintype "input"))
    )
    (net (code "9") (name "IN1") (class "Default")
      (node (ref "U20") (pin "37") (pinfunction "IO23_37") (pintype "input"))
      (node (ref "U21") (pin "2") (pinfunction "INA_2") (pintype "input"))
    )
    (net (code "10") (name "IN2") (class "Default")
      (node (ref "U20") (pin "36") (pinfunction "IO22_36") (pintype "input"))
      (node (ref "U21") (pin "3") (pinfunction "INB_3") (pintype "input"))
    )
    (net (code "11") (name "IN3") (class "Default")
      (node (ref "U20") (pin "33") (pinfunction "IO21_33") (pintype "input"))
      (node (ref "U21") (pin "6") (pinfunction "INC_6") (pintype "input"))
    )
    (net (code "12") (name "IN4") (class "Default")
      (node (ref "U20") (pin "31") (pinfunction "IO19_31") (pintype "input"))
      (node (ref "U21") (pin "7") (pinfunction "IND_7") (pintype "input"))
    )
    (net (code "13") (name "IO0") (class "Default")
      (node (ref "Q24") (pin "3") (pinfunction "C_3") (pintype "input"))
      (node (ref "U20") (pin "25") (pinfunction "IO0_25") (pintype "input"))
    )
    (net (code "14") (name "LAT") (class "Default")
      (node (ref "FPC21") (pin "8") (pinfunction "8_8") (pintype "input"))
      (node (ref "U20") (pin "14") (pinfunction "IO12_14") (pintype "input"))
    )
    (net (code "15") (name "LED") (class "Default")
      (node (ref "LED22") (pin "1") (pinfunction "K_1") (pintype "input"))
      (node (ref "U20") (pin "30") (pinfunction "IO18_30") (pintype "input"))
    )
    (net (code "16") (name "M_A+") (class "Default")
      (node (ref "FPC21") (pin "3") (pinfunction "3_3") (pintype "input"))
      (node (ref "U21") (pin "13") (pinfunction "OUTB_13") (pintype "input"))
    )
    (net (code "17") (name "M_A-") (class "Default")
      (node (ref "FPC21") (pin "4") (pinfunction "4_4") (pintype "input"))
      (node (ref "U21") (pin "16") (pinfunction "OUTA_16") (pintype "input"))
    )
    (net (code "18") (name "M_B+") (class "Default")
      (node (ref "FPC21") (pin "1") (pinfunction "1_1") (pintype "input"))
      (node (ref "U21") (pin "9") (pinfunction "OUTD_9") (pintype "input"))
    )
    (net (code "19") (name "M_B-") (class "Default")
      (node (ref "FPC21") (pin "2") (pinfunction "2_2") (pintype "input"))
      (node (ref "U21") (pin "12") (pinfunction "OUTC_12") (pintype "input"))
    )
    (net (code "20") (name "Net-(FPC21-Pad30)") (class "Default")
      (node (ref "FPC21") (pin "30") (pinfunction "30_30") (pintype "input"))
      (node (ref "R37") (pin "1") (pinfunction "1_1") (pintype "input"))
    )
    (net (code "21") (name "Net-(LED20-A)") (class "Default")
      (node (ref "LED20") (pin "2") (pinfunction "A_2") (pintype "input"))
      (node (ref "R21") (pin "2") (pinfunction "2_2") (pintype "input"))
    )
    (net (code "22") (name "Net-(LED21-A)") (class "Default")
      (node (ref "LED21") (pin "1") (pinfunction "A_1") (pintype "input"))
      (node (ref "R28") (pin "2") (pinfunction "2_2") (pintype "input"))
    )
    (net (code "23") (name "Net-(LED21-K)") (class "Default")
      (node (ref "LED21") (pin "2") (pinfunction "K_2") (pintype "input"))
      (node (ref "U22") (pin "1") (pinfunction "CHRG_1") (pintype "input"))
    )
    (net (code "24") (name "Net-(LED22-A)") (class "Default")
      (node (ref "LED22") (pin "2") (pinfunction "A_2") (pintype "input"))
      (node (ref "R25") (pin "2") (pinfunction "2_2") (pintype "input"))
    )
    (net (code "25") (name "Net-(Q1-G)") (class "Default")
      (node (ref "E20") (pin "1") (pinfunction "1_1") (pintype "input"))
      (node (ref "Q1") (pin "4") (pinfunction "G_4") (pintype "input"))
      (node (ref "R39") (pin "1") (pinfunction "1_1") (pintype "input"))
      (node (ref "SW22") (pin "1") (pinfunction "1_1") (pintype "input"))
    )
    (net (code "26") (name "Net-(Q21-G)") (class "Default")
      (node (ref "Q21") (pin "4") (pinfunction "G_4") (pintype "input"))
      (node (ref "Q23") (pin "3") (pinfunction "D_3") (pintype "input"))
      (node (ref "R38") (pin "1") (pinfunction "1_1") (pintype "input"))
    )
    (net (code "27") (name "Net-(Q24-B)") (class "Default")
      (node (ref "Q24") (pin "1") (pinfunction "B_1") (pintype "input"))
      (node (ref "R40") (pin "1") (pinfunction "1_1") (pintype "input"))
    )
    (net (code "28") (name "Net-(Q25-B)") (class "Default")
      (node (ref "Q25") (pin "1") (pinfunction "B_1") (pintype "input"))
      (node (ref "R43") (pin "1") (pinfunction "1_1") (pintype "input"))
    )
    (net (code "29") (name "Net-(U22-PROG)") (class "Default")
      (node (ref "R26") (pin "2") (pinfunction "2_2") (pintype "input"))
      (node (ref "U22") (pin "5") (pinfunction "PROG_5") (pintype "input"))
    )
    (net (code "30") (name "Net-(U23-FB)") (class "Default")
      (node (ref "R30") (pin "1") (pinfunction "1_1") (pintype "input"))
      (node (ref "R33") (pin "2") (pinfunction "2_2") (pintype "input"))
      (node (ref "U23") (pin "6") (pinfunction "FB_6") (pintype "input"))
    )
    (net (code "31") (name "Net-(U23-LX)") (class "Default")
      (node (ref "D20") (pin "2") (pinfunction "2_2") (pintype "input"))
      (node (ref "L20") (pin "2") (pinfunction "2_2") (pintype "input"))
      (node (ref "U23") (pin "8") (pinfunction "LX_8") (pintype "input"))
    )
    (net (code "32") (name "Net-(U23-OC)") (class "Default")
      (node (ref "R34") (pin "2") (pinfunction "2_2") (pintype "input"))
      (node (ref "U23") (pin "2") (pinfunction "OC_2") (pintype "input"))
    )
    (net (code "33") (name "Net-(U25-CC1)") (class "Default")
      (node (ref "R41") (pin "2") (pinfunction "2_2") (pintype "input"))
      (node (ref "U25") (pin "A5") (pinfunction "CC1_A5") (pintype "input"))
    )
    (net (code "34") (name "Net-(U25-CC2)") (class "Default")
      (node (ref "R42") (pin "1") (pinfunction "1_1") (pintype "input"))
      (node (ref "U25") (pin "B5") (pinfunction "CC2_B5") (pintype "input"))
    )
    (net (code "35") (name "Net-(U29A-INA+)") (class "Default")
      (node (ref "R31") (pin "1") (pinfunction "1_1") (pintype "input"))
      (node (ref "R36") (pin "2") (pinfunction "2_2") (pintype "input"))
      (node (ref "U29") (pin "3") (pinfunction "INA+_3") (pintype "input"))
    )
    (net (code "36") (name "PHE") (class "Default")
      (node (ref "FPC21") (pin "28") (pinfunction "28_28") (pintype "input"))
      (node (ref "R35") (pin "2") (pinfunction "2_2") (pintype "input"))
      (node (ref "U29") (pin "2") (pinfunction "INA-_2") (pintype "input"))
    )
    (net (code "37") (name "PHINT") (class "Default")
      (node (ref "R32") (pin "2") (pinfunction "2_2") (pintype "input"))
      (node (ref "U20") (pin "7") (pinfunction "IO35_7") (pintype "input"))
      (node (ref "U29") (pin "1") (pinfunction "OUTA_1") (pintype "output"))
    )
    (net (code "38") (name "POWER_ADC") (class "Default")
      (node (ref "C35") (pin "2") (pinfunction "2_2") (pintype "input"))
      (node (ref "R27") (pin "1") (pinfunction "1_1") (pintype "input"))
      (node (ref "R29") (pin "2") (pinfunction "2_2") (pintype "input"))
      (node (ref "U20") (pin "6") (pinfunction "IO34_6") (pintype "input"))
    )
    (net (code "39") (name "RXD") (class "Default")
      (node (ref "U20") (pin "34") (pinfunction "U0RXD_34") (pintype "input"))
      (node (ref "U26") (pin "2") (pinfunction "TXD_2") (pintype "input"))
    )
    (net (code "40") (name "STB1") (class "Default")
      (node (ref "FPC21") (pin "11") (pinfunction "11_11") (pintype "input"))
      (node (ref "U20") (pin "13") (pinfunction "IO14_13") (pintype "input"))
    )
    (net (code "41") (name "STB2") (class "Default")
      (node (ref "FPC21") (pin "12") (pinfunction "12_12") (pintype "input"))
      (node (ref "U20") (pin "12") (pinfunction "IO27_12") (pintype "input"))
    )
    (net (code "42") (name "STB3") (class "Default")
      (node (ref "FPC21") (pin "13") (pinfunction "13_13") (pintype "input"))
      (node (ref "U20") (pin "11") (pinfunction "IO26_11") (pintype "input"))
    )
    (net (code "43") (name "STB4") (class "Default")
      (node (ref "FPC21") (pin "17") (pinfunction "17_17") (pintype "input"))
      (node (ref "U20") (pin "10") (pinfunction "IO25_10") (pintype "input"))
    )
    (net (code "44") (name "STB5") (class "Default")
      (node (ref "FPC21") (pin "18") (pinfunction "18_18") (pintype "input"))
      (node (ref "U20") (pin "9") (pinfunction "IO33_9") (pintype "input"))
    )
    (net (code "45") (name "STB6") (class "Default")
      (node (ref "FPC21") (pin "19") (pinfunction "19_19") (pintype "input"))
      (node (ref "U20") (pin "8") (pinfunction "IO32_8") (pintype "input"))
    )
    (net (code "46") (name "THER") (class "Default")
      (node (ref "FPC21") (pin "14") (pinfunction "14_14") (pintype "input"))
      (node (ref "R22") (pin "1") (pinfunction "1_1") (pintype "input"))
      (node (ref "U20") (pin "4") (pinfunction "SENSOR_VP_4") (pintype "input"))
    )
    (net (code "47") (name "TXD") (class "Default")
      (node (ref "U20") (pin "35") (pinfunction "U0TXD_35") (pintype "input"))
      (node (ref "U26") (pin "3") (pinfunction "RXD_3") (pintype "input"))
    )
    (net (code "48") (name "UD+") (class "Default")
      (node (ref "U25") (pin "A6") (pinfunction "DP1_A6") (pintype "input"))
      (node (ref "U25") (pin "B6") (pinfunction "DP2_B6") (pintype "input"))
      (node (ref "U26") (pin "5") (pinfunction "D+_5") (pintype "input"))
    )
    (net (code "49") (name "UD-") (class "Default")
      (node (ref "U25") (pin "A7") (pinfunction "DN1_A7") (pintype "input"))
      (node (ref "U25") (pin "B7") (pinfunction "DN2_B7") (pintype "input"))
      (node (ref "U26") (pin "6") (pinfunction "D-_6") (pintype "input"))
    )
    (net (code "50") (name "VBAT") (class "Default")
      (node (ref "C33") (pin "2") (pinfunction "2_2") (pintype "input"))
      (node (ref "C34") (pin "2") (pinfunction "2_2") (pintype "input"))
      (node (ref "FPC20") (pin "2") (pinfunction "2_2") (pintype "input"))
      (node (ref "Q1") (pin "1") (pinfunction "S_1") (pintype "input"))
      (node (ref "Q1") (pin "2") (pinfunction "S_2") (pintype "input"))
      (node (ref "Q1") (pin "3") (pinfunction "S_3") (pintype "input"))
      (node (ref "R39") (pin "2") (pinfunction "2_2") (pintype "input"))
      (node (ref "U22") (pin "3") (pinfunction "BAT_3") (pintype "input"))
    )
    (net (code "51") (name "VBAT_OUT") (class "Default")
      (node (ref "C25") (pin "2") (pinfunction "2_2") (pintype "input"))
      (node (ref "C26") (pin "2") (pinfunction "2_2") (pintype "input"))
      (node (ref "C40") (pin "2") (pinfunction "2_2") (pintype "input"))
      (node (ref "Q1") (pin "5") (pinfunction "D_5") (pintype "input"))
      (node (ref "Q1") (pin "6") (pinfunction "D_6") (pintype "input"))
      (node (ref "Q1") (pin "7") (pinfunction "D_7") (pintype "input"))
      (node (ref "Q1") (pin "8") (pinfunction "D_8") (pintype "input"))
      (node (ref "Q21") (pin "1") (pinfunction "S_1") (pintype "input"))
      (node (ref "Q21") (pin "2") (pinfunction "S_2") (pintype "input"))
      (node (ref "Q21") (pin "3") (pinfunction "S_3") (pintype "input"))
      (node (ref "R27") (pin "2") (pinfunction "2_2") (pintype "input"))
      (node (ref "R38") (pin "2") (pinfunction "2_2") (pintype "input"))
      (node (ref "U21") (pin "4") (pinfunction "VDD_4") (pintype "input"))
      (node (ref "U21") (pin "8") (pinfunction "VDD_8") (pintype "input"))
      (node (ref "U24") (pin "1") (pinfunction "VIN_1") (pintype "input"))
      (node (ref "U24") (pin "3") (pinfunction "CE_3") (pintype "input"))
    )
    (net (code "52") (name "VBUS") (class "Default")
      (node (ref "C31") (pin "2") (pinfunction "2_2") (pintype "input"))
      (node (ref "C32") (pin "1") (pinfunction "1_1") (pintype "input"))
      (node (ref "R28") (pin "1") (pinfunction "1_1") (pintype "input"))
      (node (ref "U22") (pin "4") (pinfunction "VCC_4") (pintype "input"))
      (node (ref "U25") (pin "A4") (pinfunction "VBUS_A4") (pintype "input"))
      (node (ref "U25") (pin "A9") (pinfunction "VBUS_A9") (pintype "input"))
      (node (ref "U25") (pin "B4") (pinfunction "VBUS_B4") (pintype "input"))
      (node (ref "U25") (pin "B9") (pinfunction "VBUS_B9") (pintype "input"))
    )
    (net (code "53") (name "VCC_IN") (class "Default")
      (node (ref "C36") (pin "2") (pinfunction "2_2") (pintype "input"))
      (node (ref "C37") (pin "2") (pinfunction "2_2") (pintype "input"))
      (node (ref "L20") (pin "1") (pinfunction "1_1") (pintype "input"))
      (node (ref "Q21") (pin "5") (pinfunction "D_5") (pintype "input"))
      (node (ref "Q21") (pin "6") (pinfunction "D_6") (pintype "input"))
      (node (ref "Q21") (pin "7") (pinfunction "D_7") (pintype "input"))
      (node (ref "Q21") (pin "8") (pinfunction "D_8") (pintype "input"))
      (node (ref "U23") (pin "3") (pinfunction "VIN_3") (pintype "input"))
      (node (ref "U23") (pin "4") (pinfunction "EN_4") (pintype "input"))
    )
    (net (code "54") (name "VH") (class "Default")
      (node (ref "C27") (pin "2") (pinfunction "2_2") (pintype "input"))
      (node (ref "C28") (pin "2") (pinfunction "2_2") (pintype "input"))
      (node (ref "C38") (pin "2") (pinfunction "2_2") (pintype "input"))
      (node (ref "C39") (pin "2") (pinfunction "2_2") (pintype "input"))
      (node (ref "D20") (pin "1") (pinfunction "1_1") (pintype "input"))
      (node (ref "FPC21") (pin "24") (pinfunction "24_24") (pintype "input"))
      (node (ref "FPC21") (pin "25") (pinfunction "25_25") (pintype "input"))
      (node (ref "FPC21") (pin "5") (pinfunction "5_5") (pintype "input"))
      (node (ref "FPC21") (pin "6") (pinfunction "6_6") (pintype "input"))
      (node (ref "R30") (pin "2") (pinfunction "2_2") (pintype "input"))
    )
    (net (code "55") (name "VH_EN") (class "Default")
      (node (ref "Q23") (pin "1") (pinfunction "G_1") (pintype "input"))
      (node (ref "U20") (pin "28") (pinfunction "IO17_28") (pintype "input"))
    )
    (net (code "56") (name "unconnected-(FPC20-Pad3)") (class "Default")
      (node (ref "FPC20") (pin "3") (pinfunction "3_3") (pintype "input+no_connect"))
    )
    (net (code "57") (name "unconnected-(FPC20-Pad4)") (class "Default")
      (node (ref "FPC20") (pin "4") (pinfunction "4_4") (pintype "input+no_connect"))
    )
    (net (code "58") (name "unconnected-(FPC21-Pad7)") (class "Default")
      (node (ref "FPC21") (pin "7") (pinfunction "7_7") (pintype "input+no_connect"))
    )
    (net (code "59") (name "unconnected-(FPC21-Pad26)") (class "Default")
      (node (ref "FPC21") (pin "26") (pinfunction "26_26") (pintype "input+no_connect"))
    )
    (net (code "60") (name "unconnected-(FPC21-Pad27)") (class "Default")
      (node (ref "FPC21") (pin "27") (pinfunction "27_27") (pintype "input+no_connect"))
    )
    (net (code "61") (name "unconnected-(FPC21-Pad31)") (class "Default")
      (node (ref "FPC21") (pin "31") (pinfunction "31_31") (pintype "input+no_connect"))
    )
    (net (code "62") (name "unconnected-(FPC21-Pad32)") (class "Default")
      (node (ref "FPC21") (pin "32") (pinfunction "32_32") (pintype "input+no_connect"))
    )
    (net (code "63") (name "unconnected-(SW20-EP-Pad3)") (class "Default")
      (node (ref "SW20") (pin "3") (pinfunction "EP_3") (pintype "input+no_connect"))
    )
    (net (code "64") (name "unconnected-(SW22-Pad3)") (class "Default")
      (node (ref "SW22") (pin "3") (pinfunction "3_3") (pintype "input+no_connect"))
    )
    (net (code "65") (name "unconnected-(U20-CLK-Pad20)") (class "Default")
      (node (ref "U20") (pin "20") (pinfunction "CLK_20") (pintype "input+no_connect"))
    )
    (net (code "66") (name "unconnected-(U20-CMD-Pad19)") (class "Default")
      (node (ref "U20") (pin "19") (pinfunction "CMD_19") (pintype "input+no_connect"))
    )
    (net (code "67") (name "unconnected-(U20-IO2-Pad24)") (class "Default")
      (node (ref "U20") (pin "24") (pinfunction "IO2_24") (pintype "input+no_connect"))
    )
    (net (code "68") (name "unconnected-(U20-IO4-Pad26)") (class "Default")
      (node (ref "U20") (pin "26") (pinfunction "IO4_26") (pintype "input+no_connect"))
    )
    (net (code "69") (name "unconnected-(U20-IO16-Pad27)") (class "Default")
      (node (ref "U20") (pin "27") (pinfunction "IO16_27") (pintype "input+no_connect"))
    )
    (net (code "70") (name "unconnected-(U20-NC-Pad32)") (class "Default")
      (node (ref "U20") (pin "32") (pinfunction "NC_32") (pintype "input+no_connect"))
    )
    (net (code "71") (name "unconnected-(U20-SD2-Pad17)") (class "Default")
      (node (ref "U20") (pin "17") (pinfunction "SD2_17") (pintype "input+no_connect"))
    )
    (net (code "72") (name "unconnected-(U20-SD3-Pad18)") (class "Default")
      (node (ref "U20") (pin "18") (pinfunction "SD3_18") (pintype "input+no_connect"))
    )
    (net (code "73") (name "unconnected-(U20-SDI-Pad22)") (class "Default")
      (node (ref "U20") (pin "22") (pinfunction "SDI_22") (pintype "input+no_connect"))
    )
    (net (code "74") (name "unconnected-(U20-SDO-Pad21)") (class "Default")
      (node (ref "U20") (pin "21") (pinfunction "SDO_21") (pintype "input+no_connect"))
    )
    (net (code "75") (name "unconnected-(U20-SENSOR_VN-Pad5)") (class "Default")
      (node (ref "U20") (pin "5") (pinfunction "SENSOR_VN_5") (pintype "input+no_connect"))
    )
    (net (code "76") (name "unconnected-(U21-NC-Pad1)") (class "Default")
      (node (ref "U21") (pin "1") (pinfunction "NC_1") (pintype "input+no_connect"))
    )
    (net (code "77") (name "unconnected-(U21-NC-Pad5)") (class "Default")
      (node (ref "U21") (pin "5") (pinfunction "NC_5") (pintype "input+no_connect"))
    )
    (net (code "78") (name "unconnected-(U23-NC-Pad7)") (class "Default")
      (node (ref "U23") (pin "7") (pinfunction "NC_7") (pintype "input+no_connect"))
    )
    (net (code "79") (name "unconnected-(U24-NC-Pad4)") (class "Default")
      (node (ref "U24") (pin "4") (pinfunction "NC_4") (pintype "input+no_connect"))
    )
    (net (code "80") (name "unconnected-(U25-SBU1-PadA8)") (class "Default")
      (node (ref "U25") (pin "A8") (pinfunction "SBU1_A8") (pintype "input+no_connect"))
    )
    (net (code "81") (name "unconnected-(U25-SBU2-PadB8)") (class "Default")
      (node (ref "U25") (pin "B8") (pinfunction "SBU2_B8") (pintype "input+no_connect"))
    )
    (net (code "82") (name "unconnected-(U26-CTS#-Pad9)") (class "Default")
      (node (ref "U26") (pin "9") (pinfunction "CTS#_9") (pintype "input+no_connect"))
    )
    (net (code "83") (name "unconnected-(U26-DCD#-Pad12)") (class "Default")
      (node (ref "U26") (pin "12") (pinfunction "DCD#_12") (pintype "input+no_connect"))
    )
    (net (code "84") (name "unconnected-(U26-DSR#-Pad10)") (class "Default")
      (node (ref "U26") (pin "10") (pinfunction "DSR#_10") (pintype "input+no_connect"))
    )
    (net (code "85") (name "unconnected-(U26-NC.-Pad7)") (class "Default")
      (node (ref "U26") (pin "7") (pinfunction "NC._7") (pintype "input+no_connect"))
    )
    (net (code "86") (name "unconnected-(U26-NC.-Pad8)") (class "Default")
      (node (ref "U26") (pin "8") (pinfunction "NC._8") (pintype "input+no_connect"))
    )
    (net (code "87") (name "unconnected-(U26-R232-Pad15)") (class "Default")
      (node (ref "U26") (pin "15") (pinfunction "R232_15") (pintype "input+no_connect"))
    )
    (net (code "88") (name "unconnected-(U26-RI#-Pad11)") (class "Default")
      (node (ref "U26") (pin "11") (pinfunction "RI#_11") (pintype "input+no_connect"))
    )
    (net (code "89") (name "unconnected-(U29B-INB+-Pad5)") (class "Default")
      (node (ref "U29") (pin "5") (pinfunction "INB+_5") (pintype "input+no_connect"))
    )
    (net (code "90") (name "unconnected-(U29B-INB--Pad6)") (class "Default")
      (node (ref "U29") (pin "6") (pinfunction "INB-_6") (pintype "input+no_connect"))
    )
    (net (code "91") (name "unconnected-(U29B-OUTB-Pad7)") (class "Default")
      (node (ref "U29") (pin "7") (pinfunction "OUTB_7") (pintype "output+no_connect"))
    )
  )
)
